# beaglebone-interface-hw.net
KiCad netlist of a schematic drawn in Altium Designer
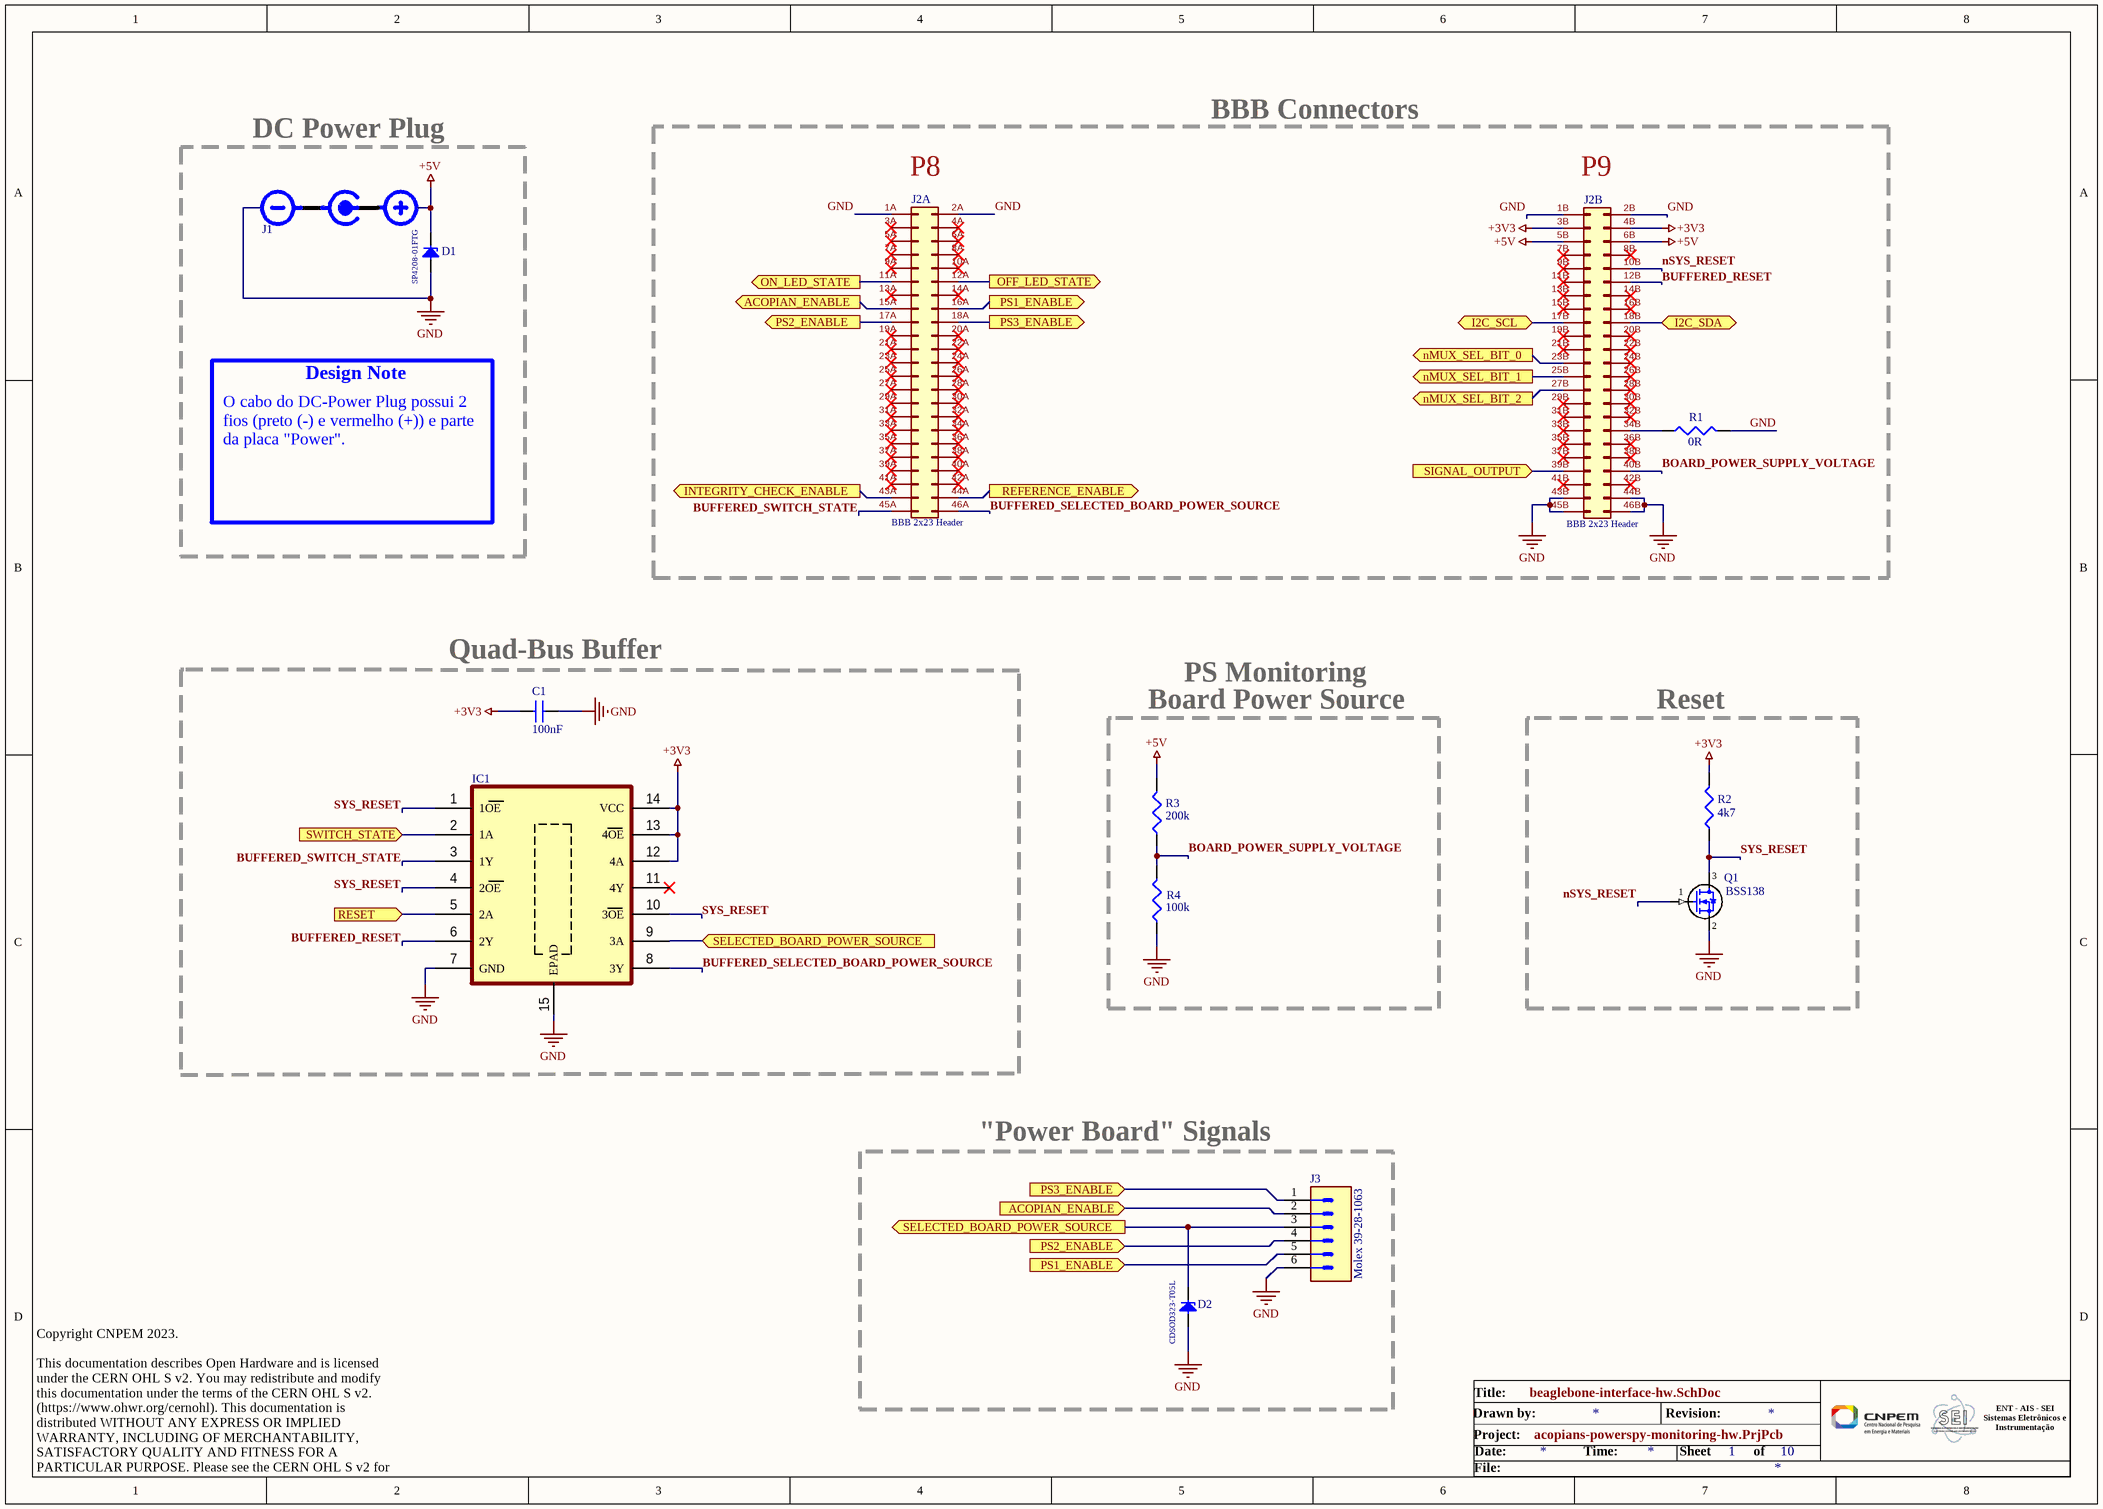
[diagram p0: beaglebone-interface-hw.SchDoc]

(export (version "E")
  (design (tool "Eeschema 10.0.6"))
  (components
    (comp (ref "C1")
      (value "100nF")
      (footprint "C0805")
      (libsource (lib "acopians-powerspy-monitoring-hw-library-schematic") (part "Capacitor 100nF"))
    )
    (comp (ref "D1")
      (value "SP4208-01FTG")
      (footprint "SOD-323")
      (description "Unidirectional TVS Diode")
      (libsource (lib "acopians-powerspy-monitoring-hw-library-schematic") (part "SP4208-01FTG"))
    )
    (comp (ref "D2")
      (value "CDSOD323-T05L")
      (footprint "SOD-323")
      (description "Unidirectional TVS Diode")
      (libsource (lib "acopians-powerspy-monitoring-hw-library-schematic") (part "CDSOD323-T05L"))
    )
    (comp (ref "IC1")
      (value "SN74LV125ARGYR")
      (footprint "VQFN-14")
      (description "Quadruple Bus Buffer Gates With 3-State Outputs")
      (libsource (lib "acopians-powerspy-monitoring-hw-library-schematic") (part "SN74LV125ARGYR"))
    )
    (comp (ref "J1")
      (value "DC Power Plug")
      (libsource (lib "acopians-powerspy-monitoring-hw-library-schematic") (part "DC Power Plug"))
    )
    (comp (ref "J2")
      (value "BBB 2x23 Header")
      (footprint "BBB 2x23 Header")
      (libsource (lib "acopians-powerspy-monitoring-hw-library-schematic") (part "BBB 2x23 Header"))
    )
    (comp (ref "J3")
      (value "Molex 39-28-1063")
      (footprint "MOLEX_39-28-1063")
      (libsource (lib "acopians-powerspy-monitoring-hw-library-schematic") (part "Connector 6 Male"))
    )
    (comp (ref "Q1")
      (value "BSS138")
      (footprint "SOT_23_3")
      (description "MOSFET N-Channel")
      (libsource (lib "acopians-powerspy-monitoring-hw-library-schematic") (part "BSS138"))
    )
    (comp (ref "R1")
      (value "0R")
      (footprint "R1210")
      (description "Size 1210")
      (libsource (lib "acopians-powerspy-monitoring-hw-library-schematic") (part "Resistor 0R"))
    )
    (comp (ref "R2")
      (value "4k7")
      (footprint "Resistor 0805")
      (description "Size 0805")
      (libsource (lib "acopians-powerspy-monitoring-hw-library-schematic") (part "Resistor 4k7"))
    )
    (comp (ref "R3")
      (value "200k")
      (footprint "Resistor 0805")
      (description "Size 0805")
      (libsource (lib "acopians-powerspy-monitoring-hw-library-schematic") (part "Resistor 200k"))
    )
    (comp (ref "R4")
      (value "100k")
      (footprint "Resistor 0805")
      (libsource (lib "acopians-powerspy-monitoring-hw-library-schematic") (part "Resistor 100k"))
    )
  )
  (nets
    (net (code "1") (name "+3V3") (class "Default")
      (node (ref "C1") (pin "2") (pinfunction "2_2") (pintype "passive"))
      (node (ref "IC1") (pin "12") (pinfunction "4A_12") (pintype "passive"))
      (node (ref "IC1") (pin "13") (pinfunction "4OE_13") (pintype "passive"))
      (node (ref "IC1") (pin "14") (pinfunction "VCC_14") (pintype "passive"))
      (node (ref "J2") (pin "3B") (pinfunction "Pin_3_3B") (pintype "passive"))
      (node (ref "J2") (pin "4B") (pinfunction "Pin_4_4B") (pintype "passive"))
      (node (ref "R2") (pin "2") (pinfunction "2_2") (pintype "passive"))
    )
    (net (code "2") (name "+5V") (class "Default")
      (node (ref "D1") (pin "1") (pintype "passive"))
      (node (ref "J1") (pin "2") (pinfunction "+VCC_2") (pintype "passive"))
      (node (ref "J2") (pin "5B") (pinfunction "Pin_5_5B") (pintype "passive"))
      (node (ref "J2") (pin "6B") (pinfunction "Pin_6_6B") (pintype "passive"))
      (node (ref "R3") (pin "2") (pinfunction "2_2") (pintype "passive"))
    )
    (net (code "3") (name "/ACOPIAN_ENABLE") (class "Default")
      (node (ref "J2") (pin "15A") (pinfunction "Pin_15_15A") (pintype "passive"))
      (node (ref "J3") (pin "2") (pinfunction "2_2") (pintype "passive"))
    )
    (net (code "4") (name "/BOARD_POWER_SUPPLY_VOLTAGE") (class "Default")
      (node (ref "J2") (pin "40B") (pinfunction "Pin_40_40B") (pintype "passive"))
      (node (ref "R3") (pin "1") (pinfunction "1_1") (pintype "passive"))
      (node (ref "R4") (pin "2") (pinfunction "2_2") (pintype "passive"))
    )
    (net (code "5") (name "/BUFFERED_RESET") (class "Default")
      (node (ref "IC1") (pin "6") (pinfunction "2Y_6") (pintype "passive"))
      (node (ref "J2") (pin "12B") (pinfunction "Pin_12_12B") (pintype "passive"))
    )
    (net (code "6") (name "/BUFFERED_SELECTED_BOARD_POWER_SOURCE") (class "Default")
      (node (ref "IC1") (pin "8") (pinfunction "3Y_8") (pintype "passive"))
      (node (ref "J2") (pin "46A") (pinfunction "Pin_46_46A") (pintype "passive"))
    )
    (net (code "7") (name "/BUFFERED_SWITCH_STATE") (class "Default")
      (node (ref "IC1") (pin "3") (pinfunction "1Y_3") (pintype "passive"))
      (node (ref "J2") (pin "45A") (pinfunction "Pin_45_45A") (pintype "passive"))
    )
    (net (code "8") (name "/I2C_SCL") (class "Default")
      (node (ref "J2") (pin "17B") (pinfunction "Pin_17_17B") (pintype "passive"))
    )
    (net (code "9") (name "/I2C_SDA") (class "Default")
      (node (ref "J2") (pin "18B") (pinfunction "Pin_18_18B") (pintype "passive"))
    )
    (net (code "10") (name "/INTEGRITY_CHECK_ENABLE") (class "Default")
      (node (ref "J2") (pin "43A") (pinfunction "Pin_43_43A") (pintype "passive"))
    )
    (net (code "11") (name "/OFF_LED_STATE") (class "Default")
      (node (ref "J2") (pin "12A") (pinfunction "Pin_12_12A") (pintype "passive"))
    )
    (net (code "12") (name "/ON_LED_STATE") (class "Default")
      (node (ref "J2") (pin "11A") (pinfunction "Pin_11_11A") (pintype "passive"))
    )
    (net (code "13") (name "/PS1_ENABLE") (class "Default")
      (node (ref "J2") (pin "16A") (pinfunction "Pin_16_16A") (pintype "passive"))
      (node (ref "J3") (pin "5") (pinfunction "5_5") (pintype "passive"))
    )
    (net (code "14") (name "/PS2_ENABLE") (class "Default")
      (node (ref "J2") (pin "17A") (pinfunction "Pin_17_17A") (pintype "passive"))
      (node (ref "J3") (pin "4") (pinfunction "4_4") (pintype "passive"))
    )
    (net (code "15") (name "/PS3_ENABLE") (class "Default")
      (node (ref "J2") (pin "18A") (pinfunction "Pin_18_18A") (pintype "passive"))
      (node (ref "J3") (pin "1") (pinfunction "1_1") (pintype "passive"))
    )
    (net (code "16") (name "/REFERENCE_ENABLE") (class "Default")
      (node (ref "J2") (pin "44A") (pinfunction "Pin_44_44A") (pintype "passive"))
    )
    (net (code "17") (name "/RESET") (class "Default")
      (node (ref "IC1") (pin "5") (pinfunction "2A_5") (pintype "passive"))
    )
    (net (code "18") (name "/SELECTED_BOARD_POWER_SOURCE") (class "Default")
      (node (ref "D2") (pin "1") (pintype "passive"))
      (node (ref "IC1") (pin "9") (pinfunction "3A_9") (pintype "passive"))
      (node (ref "J3") (pin "3") (pinfunction "3_3") (pintype "passive"))
    )
    (net (code "19") (name "/SIGNAL_OUTPUT") (class "Default")
      (node (ref "J2") (pin "39B") (pinfunction "Pin_39_39B") (pintype "passive"))
    )
    (net (code "20") (name "/SWITCH_STATE") (class "Default")
      (node (ref "IC1") (pin "2") (pinfunction "1A_2") (pintype "passive"))
    )
    (net (code "21") (name "/SYS_RESET") (class "Default")
      (node (ref "IC1") (pin "1") (pinfunction "1OE_1") (pintype "passive"))
      (node (ref "IC1") (pin "10") (pinfunction "3OE_10") (pintype "passive"))
      (node (ref "IC1") (pin "4") (pinfunction "2OE_4") (pintype "passive"))
      (node (ref "Q1") (pin "3") (pinfunction "D_3") (pintype "passive"))
      (node (ref "R2") (pin "1") (pinfunction "1_1") (pintype "passive"))
    )
    (net (code "22") (name "/nMUX_SEL_BIT_0") (class "Default")
      (node (ref "J2") (pin "23B") (pinfunction "Pin_23_23B") (pintype "passive"))
    )
    (net (code "23") (name "/nMUX_SEL_BIT_1") (class "Default")
      (node (ref "J2") (pin "25B") (pinfunction "Pin_25_25B") (pintype "passive"))
    )
    (net (code "24") (name "/nMUX_SEL_BIT_2") (class "Default")
      (node (ref "J2") (pin "27B") (pinfunction "Pin_27_27B") (pintype "passive"))
    )
    (net (code "25") (name "/nSYS_RESET") (class "Default")
      (node (ref "J2") (pin "10B") (pinfunction "Pin_10_10B") (pintype "passive"))
      (node (ref "Q1") (pin "1") (pinfunction "G_1") (pintype "input"))
    )
    (net (code "26") (name "GND") (class "Default")
      (node (ref "C1") (pin "1") (pinfunction "1_1") (pintype "passive"))
      (node (ref "D1") (pin "2") (pintype "passive"))
      (node (ref "D2") (pin "2") (pintype "passive"))
      (node (ref "IC1") (pin "15") (pinfunction "EPAD_15") (pintype "passive"))
      (node (ref "IC1") (pin "7") (pinfunction "GND_7") (pintype "passive"))
      (node (ref "J1") (pin "1") (pinfunction "GND_1") (pintype "passive"))
      (node (ref "J2") (pin "1A") (pinfunction "Pin_1_1A") (pintype "passive"))
      (node (ref "J2") (pin "1B") (pinfunction "Pin_1_1B") (pintype "passive"))
      (node (ref "J2") (pin "2A") (pinfunction "Pin_2_2A") (pintype "passive"))
      (node (ref "J2") (pin "2B") (pinfunction "Pin_2_2B") (pintype "passive"))
      (node (ref "J2") (pin "43B") (pinfunction "Pin_43_43B") (pintype "passive"))
      (node (ref "J2") (pin "44B") (pinfunction "Pin_44_44B") (pintype "passive"))
      (node (ref "J2") (pin "45B") (pinfunction "Pin_45_45B") (pintype "passive"))
      (node (ref "J2") (pin "46B") (pinfunction "Pin_46_46B") (pintype "passive"))
      (node (ref "J3") (pin "6") (pinfunction "6_6") (pintype "passive"))
      (node (ref "Q1") (pin "2") (pinfunction "S_2") (pintype "passive"))
      (node (ref "R1") (pin "2") (pinfunction "2_2") (pintype "passive"))
      (node (ref "R4") (pin "1") (pinfunction "1_1") (pintype "passive"))
    )
    (net (code "27") (name "Net-(J2B-Pin_34)") (class "Default")
      (node (ref "J2") (pin "34B") (pinfunction "Pin_34_34B") (pintype "passive"))
      (node (ref "R1") (pin "1") (pinfunction "1_1") (pintype "passive"))
    )
    (net (code "28") (name "unconnected-(IC1-4Y-Pad11)") (class "Default")
      (node (ref "IC1") (pin "11") (pinfunction "4Y_11") (pintype "passive+no_connect"))
    )
    (net (code "29") (name "unconnected-(J2A-Pin_3-Pad3A)") (class "Default")
      (node (ref "J2") (pin "3A") (pinfunction "Pin_3_3A") (pintype "passive+no_connect"))
    )
    (net (code "30") (name "unconnected-(J2A-Pin_4-Pad4A)") (class "Default")
      (node (ref "J2") (pin "4A") (pinfunction "Pin_4_4A") (pintype "passive+no_connect"))
    )
    (net (code "31") (name "unconnected-(J2A-Pin_5-Pad5A)") (class "Default")
      (node (ref "J2") (pin "5A") (pinfunction "Pin_5_5A") (pintype "passive+no_connect"))
    )
    (net (code "32") (name "unconnected-(J2A-Pin_6-Pad6A)") (class "Default")
      (node (ref "J2") (pin "6A") (pinfunction "Pin_6_6A") (pintype "passive+no_connect"))
    )
    (net (code "33") (name "unconnected-(J2A-Pin_7-Pad7A)") (class "Default")
      (node (ref "J2") (pin "7A") (pinfunction "Pin_7_7A") (pintype "passive+no_connect"))
    )
    (net (code "34") (name "unconnected-(J2A-Pin_8-Pad8A)") (class "Default")
      (node (ref "J2") (pin "8A") (pinfunction "Pin_8_8A") (pintype "passive+no_connect"))
    )
    (net (code "35") (name "unconnected-(J2A-Pin_9-Pad9A)") (class "Default")
      (node (ref "J2") (pin "9A") (pinfunction "Pin_9_9A") (pintype "passive+no_connect"))
    )
    (net (code "36") (name "unconnected-(J2A-Pin_10-Pad10A)") (class "Default")
      (node (ref "J2") (pin "10A") (pinfunction "Pin_10_10A") (pintype "passive+no_connect"))
    )
    (net (code "37") (name "unconnected-(J2A-Pin_13-Pad13A)") (class "Default")
      (node (ref "J2") (pin "13A") (pinfunction "Pin_13_13A") (pintype "passive+no_connect"))
    )
    (net (code "38") (name "unconnected-(J2A-Pin_14-Pad14A)") (class "Default")
      (node (ref "J2") (pin "14A") (pinfunction "Pin_14_14A") (pintype "passive+no_connect"))
    )
    (net (code "39") (name "unconnected-(J2A-Pin_19-Pad19A)") (class "Default")
      (node (ref "J2") (pin "19A") (pinfunction "Pin_19_19A") (pintype "passive+no_connect"))
    )
    (net (code "40") (name "unconnected-(J2A-Pin_20-Pad20A)") (class "Default")
      (node (ref "J2") (pin "20A") (pinfunction "Pin_20_20A") (pintype "passive+no_connect"))
    )
    (net (code "41") (name "unconnected-(J2A-Pin_21-Pad21A)") (class "Default")
      (node (ref "J2") (pin "21A") (pinfunction "Pin_21_21A") (pintype "passive+no_connect"))
    )
    (net (code "42") (name "unconnected-(J2A-Pin_22-Pad22A)") (class "Default")
      (node (ref "J2") (pin "22A") (pinfunction "Pin_22_22A") (pintype "passive+no_connect"))
    )
    (net (code "43") (name "unconnected-(J2A-Pin_23-Pad23A)") (class "Default")
      (node (ref "J2") (pin "23A") (pinfunction "Pin_23_23A") (pintype "passive+no_connect"))
    )
    (net (code "44") (name "unconnected-(J2A-Pin_24-Pad24A)") (class "Default")
      (node (ref "J2") (pin "24A") (pinfunction "Pin_24_24A") (pintype "passive+no_connect"))
    )
    (net (code "45") (name "unconnected-(J2A-Pin_25-Pad25A)") (class "Default")
      (node (ref "J2") (pin "25A") (pinfunction "Pin_25_25A") (pintype "passive+no_connect"))
    )
    (net (code "46") (name "unconnected-(J2A-Pin_26-Pad26A)") (class "Default")
      (node (ref "J2") (pin "26A") (pinfunction "Pin_26_26A") (pintype "passive+no_connect"))
    )
    (net (code "47") (name "unconnected-(J2A-Pin_27-Pad27A)") (class "Default")
      (node (ref "J2") (pin "27A") (pinfunction "Pin_27_27A") (pintype "passive+no_connect"))
    )
    (net (code "48") (name "unconnected-(J2A-Pin_28-Pad28A)") (class "Default")
      (node (ref "J2") (pin "28A") (pinfunction "Pin_28_28A") (pintype "passive+no_connect"))
    )
    (net (code "49") (name "unconnected-(J2A-Pin_29-Pad29A)") (class "Default")
      (node (ref "J2") (pin "29A") (pinfunction "Pin_29_29A") (pintype "passive+no_connect"))
    )
    (net (code "50") (name "unconnected-(J2A-Pin_30-Pad30A)") (class "Default")
      (node (ref "J2") (pin "30A") (pinfunction "Pin_30_30A") (pintype "passive+no_connect"))
    )
    (net (code "51") (name "unconnected-(J2A-Pin_31-Pad31A)") (class "Default")
      (node (ref "J2") (pin "31A") (pinfunction "Pin_31_31A") (pintype "passive+no_connect"))
    )
    (net (code "52") (name "unconnected-(J2A-Pin_32-Pad32A)") (class "Default")
      (node (ref "J2") (pin "32A") (pinfunction "Pin_32_32A") (pintype "passive+no_connect"))
    )
    (net (code "53") (name "unconnected-(J2A-Pin_33-Pad33A)") (class "Default")
      (node (ref "J2") (pin "33A") (pinfunction "Pin_33_33A") (pintype "passive+no_connect"))
    )
    (net (code "54") (name "unconnected-(J2A-Pin_34-Pad34A)") (class "Default")
      (node (ref "J2") (pin "34A") (pinfunction "Pin_34_34A") (pintype "passive+no_connect"))
    )
    (net (code "55") (name "unconnected-(J2A-Pin_35-Pad35A)") (class "Default")
      (node (ref "J2") (pin "35A") (pinfunction "Pin_35_35A") (pintype "passive+no_connect"))
    )
    (net (code "56") (name "unconnected-(J2A-Pin_36-Pad36A)") (class "Default")
      (node (ref "J2") (pin "36A") (pinfunction "Pin_36_36A") (pintype "passive+no_connect"))
    )
    (net (code "57") (name "unconnected-(J2A-Pin_37-Pad37A)") (class "Default")
      (node (ref "J2") (pin "37A") (pinfunction "Pin_37_37A") (pintype "passive+no_connect"))
    )
    (net (code "58") (name "unconnected-(J2A-Pin_38-Pad38A)") (class "Default")
      (node (ref "J2") (pin "38A") (pinfunction "Pin_38_38A") (pintype "passive+no_connect"))
    )
    (net (code "59") (name "unconnected-(J2A-Pin_39-Pad39A)") (class "Default")
      (node (ref "J2") (pin "39A") (pinfunction "Pin_39_39A") (pintype "passive+no_connect"))
    )
    (net (code "60") (name "unconnected-(J2A-Pin_40-Pad40A)") (class "Default")
      (node (ref "J2") (pin "40A") (pinfunction "Pin_40_40A") (pintype "passive+no_connect"))
    )
    (net (code "61") (name "unconnected-(J2A-Pin_41-Pad41A)") (class "Default")
      (node (ref "J2") (pin "41A") (pinfunction "Pin_41_41A") (pintype "passive+no_connect"))
    )
    (net (code "62") (name "unconnected-(J2A-Pin_42-Pad42A)") (class "Default")
      (node (ref "J2") (pin "42A") (pinfunction "Pin_42_42A") (pintype "passive+no_connect"))
    )
    (net (code "63") (name "unconnected-(J2B-Pin_7-Pad7B)") (class "Default")
      (node (ref "J2") (pin "7B") (pinfunction "Pin_7_7B") (pintype "passive+no_connect"))
    )
    (net (code "64") (name "unconnected-(J2B-Pin_8-Pad8B)") (class "Default")
      (node (ref "J2") (pin "8B") (pinfunction "Pin_8_8B") (pintype "passive+no_connect"))
    )
    (net (code "65") (name "unconnected-(J2B-Pin_9-Pad9B)") (class "Default")
      (node (ref "J2") (pin "9B") (pinfunction "Pin_9_9B") (pintype "passive+no_connect"))
    )
    (net (code "66") (name "unconnected-(J2B-Pin_11-Pad11B)") (class "Default")
      (node (ref "J2") (pin "11B") (pinfunction "Pin_11_11B") (pintype "passive+no_connect"))
    )
    (net (code "67") (name "unconnected-(J2B-Pin_13-Pad13B)") (class "Default")
      (node (ref "J2") (pin "13B") (pinfunction "Pin_13_13B") (pintype "passive+no_connect"))
    )
    (net (code "68") (name "unconnected-(J2B-Pin_14-Pad14B)") (class "Default")
      (node (ref "J2") (pin "14B") (pinfunction "Pin_14_14B") (pintype "passive+no_connect"))
    )
    (net (code "69") (name "unconnected-(J2B-Pin_15-Pad15B)") (class "Default")
      (node (ref "J2") (pin "15B") (pinfunction "Pin_15_15B") (pintype "passive+no_connect"))
    )
    (net (code "70") (name "unconnected-(J2B-Pin_16-Pad16B)") (class "Default")
      (node (ref "J2") (pin "16B") (pinfunction "Pin_16_16B") (pintype "passive+no_connect"))
    )
    (net (code "71") (name "unconnected-(J2B-Pin_19-Pad19B)") (class "Default")
      (node (ref "J2") (pin "19B") (pinfunction "Pin_19_19B") (pintype "passive+no_connect"))
    )
    (net (code "72") (name "unconnected-(J2B-Pin_20-Pad20B)") (class "Default")
      (node (ref "J2") (pin "20B") (pinfunction "Pin_20_20B") (pintype "passive+no_connect"))
    )
    (net (code "73") (name "unconnected-(J2B-Pin_21-Pad21B)") (class "Default")
      (node (ref "J2") (pin "21B") (pinfunction "Pin_21_21B") (pintype "passive+no_connect"))
    )
    (net (code "74") (name "unconnected-(J2B-Pin_22-Pad22B)") (class "Default")
      (node (ref "J2") (pin "22B") (pinfunction "Pin_22_22B") (pintype "passive+no_connect"))
    )
    (net (code "75") (name "unconnected-(J2B-Pin_24-Pad24B)") (class "Default")
      (node (ref "J2") (pin "24B") (pinfunction "Pin_24_24B") (pintype "passive+no_connect"))
    )
    (net (code "76") (name "unconnected-(J2B-Pin_26-Pad26B)") (class "Default")
      (node (ref "J2") (pin "26B") (pinfunction "Pin_26_26B") (pintype "passive+no_connect"))
    )
    (net (code "77") (name "unconnected-(J2B-Pin_28-Pad28B)") (class "Default")
      (node (ref "J2") (pin "28B") (pinfunction "Pin_28_28B") (pintype "passive+no_connect"))
    )
    (net (code "78") (name "unconnected-(J2B-Pin_29-Pad29B)") (class "Default")
      (node (ref "J2") (pin "29B") (pinfunction "Pin_29_29B") (pintype "passive+no_connect"))
    )
    (net (code "79") (name "unconnected-(J2B-Pin_30-Pad30B)") (class "Default")
      (node (ref "J2") (pin "30B") (pinfunction "Pin_30_30B") (pintype "passive+no_connect"))
    )
    (net (code "80") (name "unconnected-(J2B-Pin_31-Pad31B)") (class "Default")
      (node (ref "J2") (pin "31B") (pinfunction "Pin_31_31B") (pintype "passive+no_connect"))
    )
    (net (code "81") (name "unconnected-(J2B-Pin_32-Pad32B)") (class "Default")
      (node (ref "J2") (pin "32B") (pinfunction "Pin_32_32B") (pintype "passive+no_connect"))
    )
    (net (code "82") (name "unconnected-(J2B-Pin_33-Pad33B)") (class "Default")
      (node (ref "J2") (pin "33B") (pinfunction "Pin_33_33B") (pintype "passive+no_connect"))
    )
    (net (code "83") (name "unconnected-(J2B-Pin_35-Pad35B)") (class "Default")
      (node (ref "J2") (pin "35B") (pinfunction "Pin_35_35B") (pintype "passive+no_connect"))
    )
    (net (code "84") (name "unconnected-(J2B-Pin_36-Pad36B)") (class "Default")
      (node (ref "J2") (pin "36B") (pinfunction "Pin_36_36B") (pintype "passive+no_connect"))
    )
    (net (code "85") (name "unconnected-(J2B-Pin_37-Pad37B)") (class "Default")
      (node (ref "J2") (pin "37B") (pinfunction "Pin_37_37B") (pintype "passive+no_connect"))
    )
    (net (code "86") (name "unconnected-(J2B-Pin_38-Pad38B)") (class "Default")
      (node (ref "J2") (pin "38B") (pinfunction "Pin_38_38B") (pintype "passive+no_connect"))
    )
    (net (code "87") (name "unconnected-(J2B-Pin_41-Pad41B)") (class "Default")
      (node (ref "J2") (pin "41B") (pinfunction "Pin_41_41B") (pintype "passive+no_connect"))
    )
    (net (code "88") (name "unconnected-(J2B-Pin_42-Pad42B)") (class "Default")
      (node (ref "J2") (pin "42B") (pinfunction "Pin_42_42B") (pintype "passive+no_connect"))
    )
  )
)
